# 16n.net
KiCad netlist of a schematic drawn in EAGLE
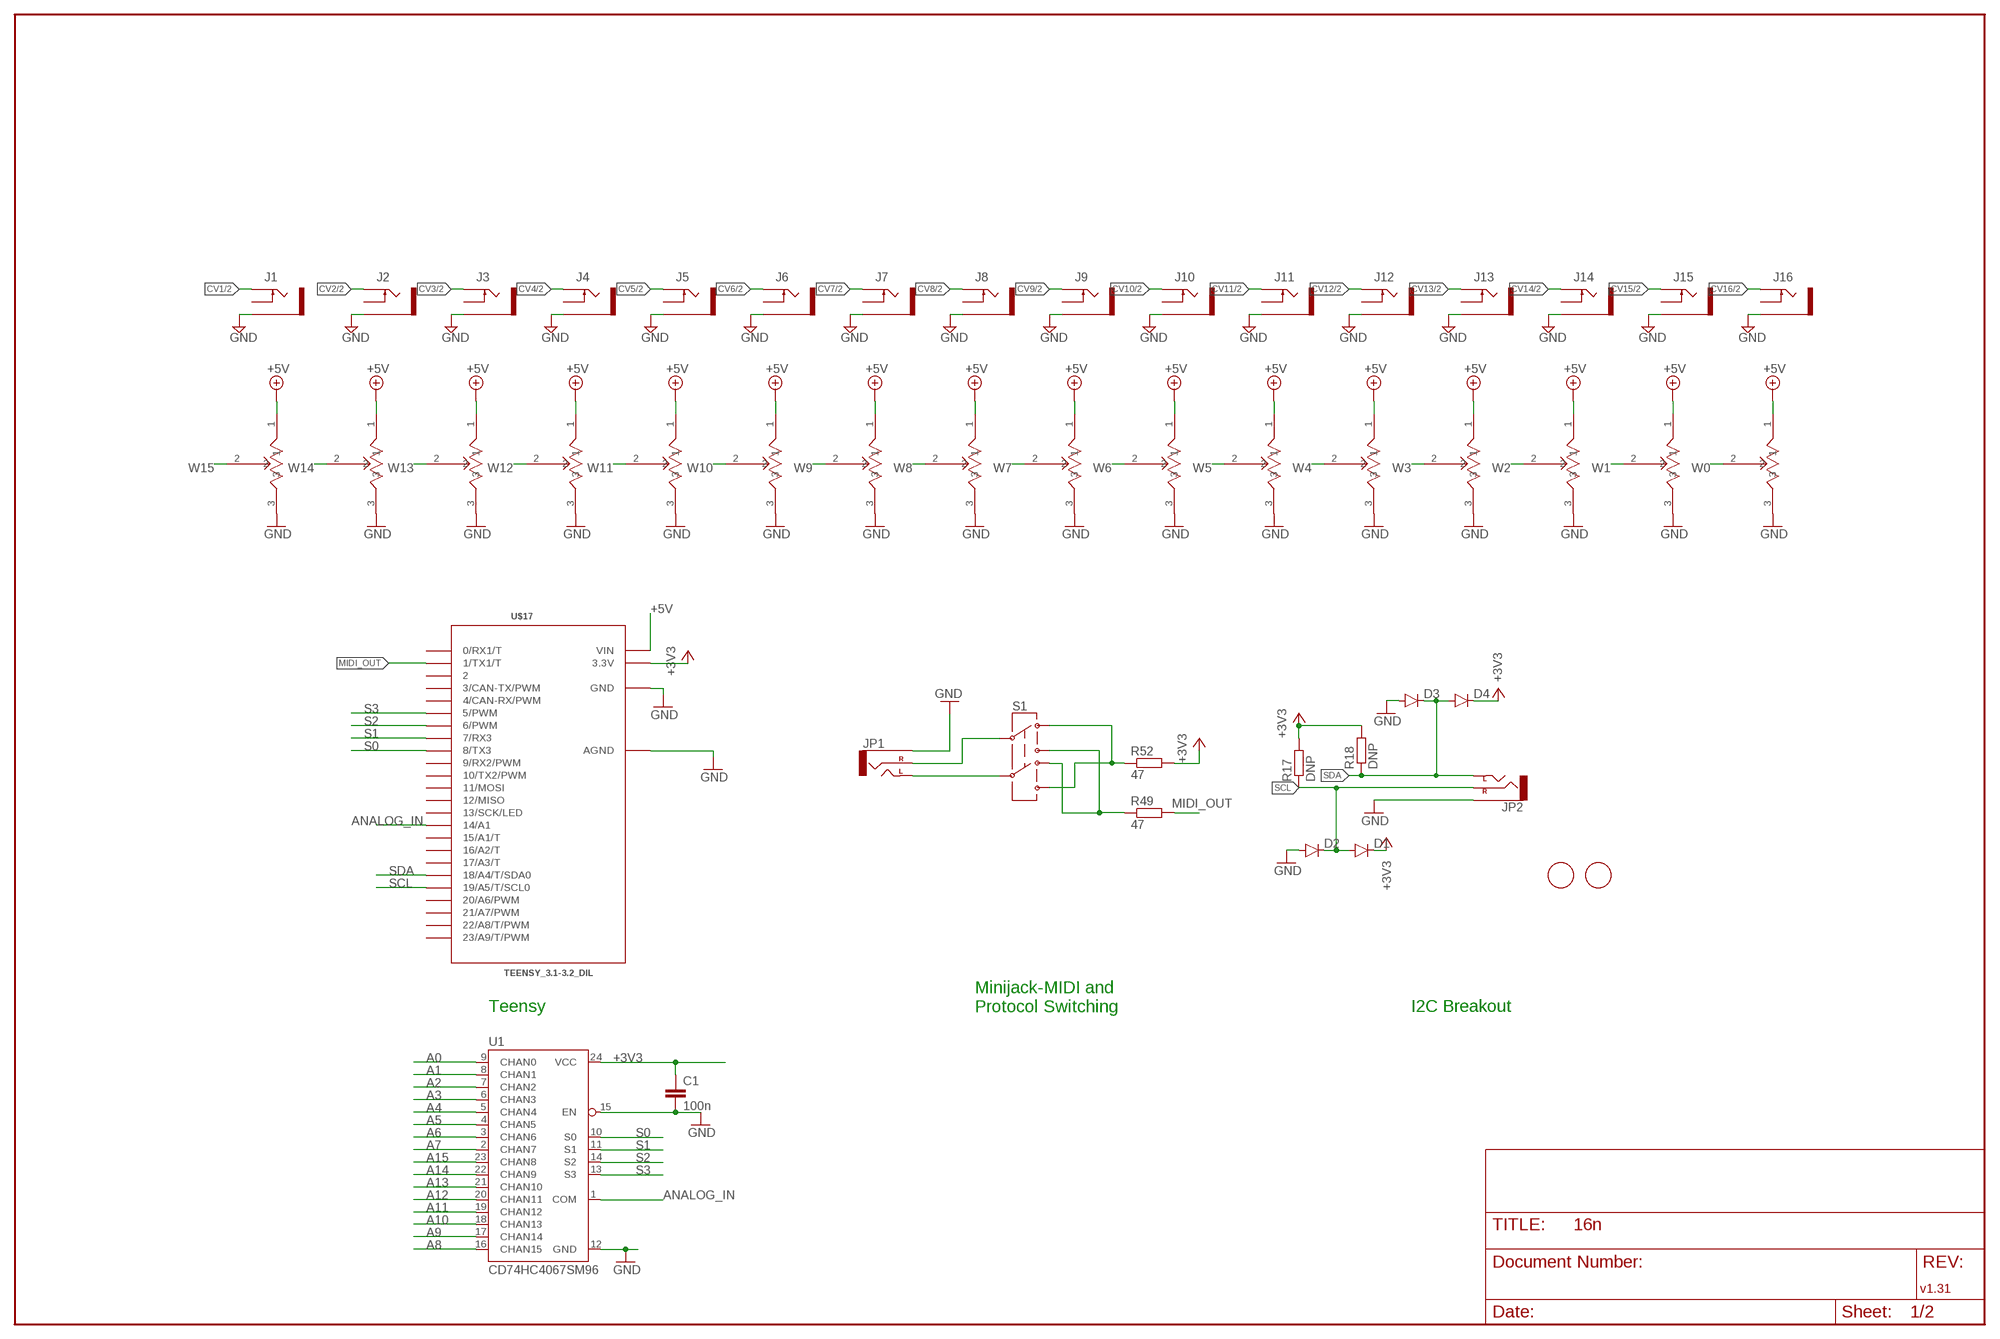
[diagram p0: schematic, sheet 1]
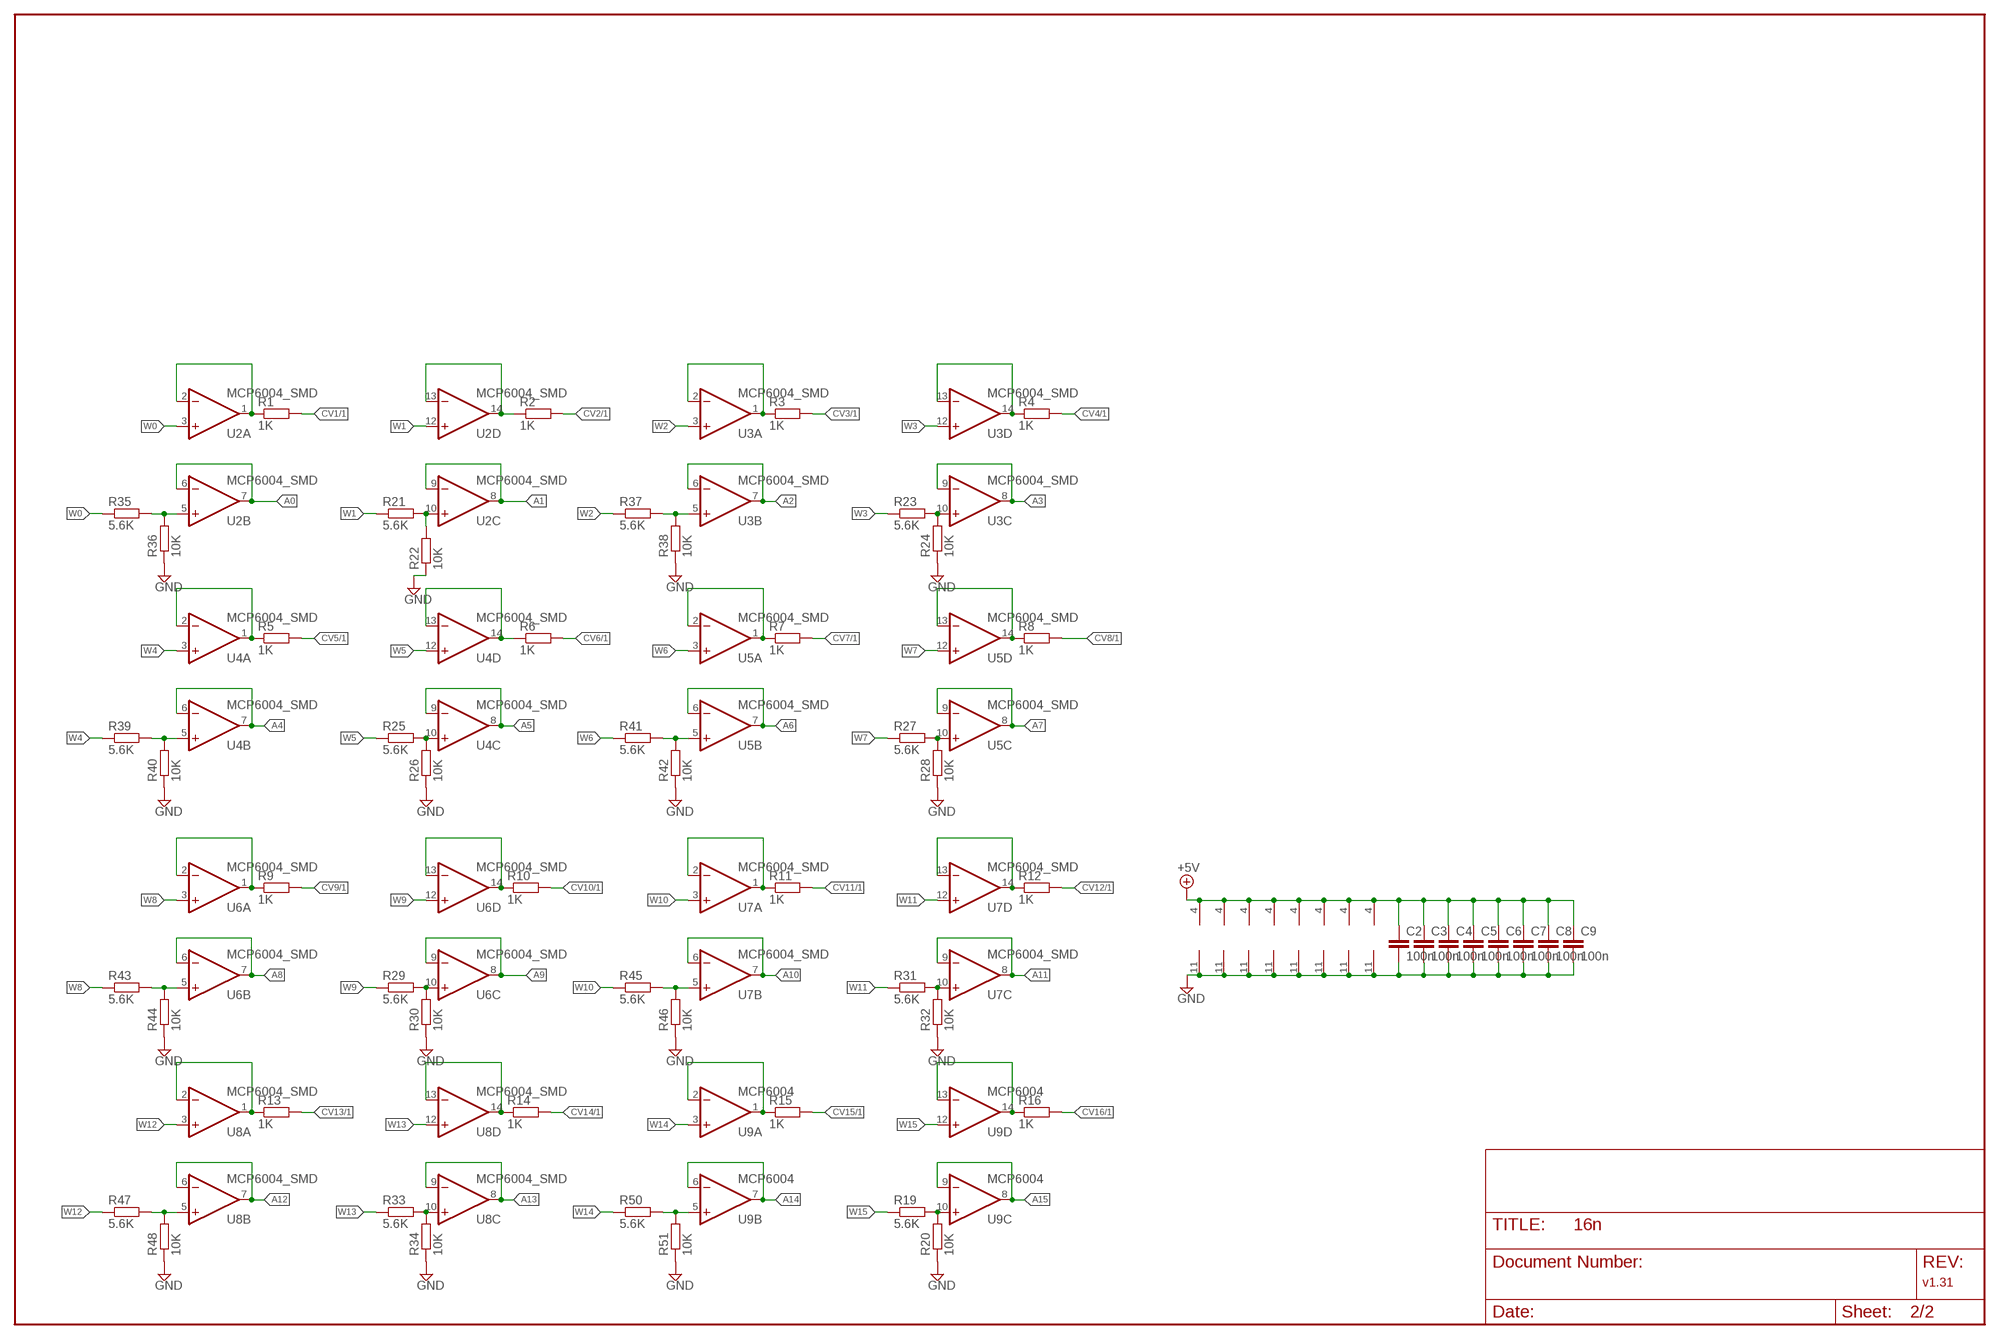
[diagram p1: schematic, sheet 2]

(export (version "E")
  (design (tool "Eeschema 10.0.6"))
  (components
    (comp (ref "C1")
      (value "100n")
      (footprint "eagle-import:C0805")
      (libsource (lib "eagle-import") (part "C-EUC0805"))
    )
    (comp (ref "D1")
      (value "DIODESOD123")
      (footprint "eagle-import:SOD-123")
      (libsource (lib "eagle-import") (part "DIODESOD123"))
    )
    (comp (ref "D2")
      (value "DIODESOD123")
      (footprint "eagle-import:SOD-123")
      (libsource (lib "eagle-import") (part "DIODESOD123"))
    )
    (comp (ref "D3")
      (value "DIODESOD123")
      (footprint "eagle-import:SOD-123")
      (libsource (lib "eagle-import") (part "DIODESOD123"))
    )
    (comp (ref "D4")
      (value "DIODESOD123")
      (footprint "eagle-import:SOD-123")
      (libsource (lib "eagle-import") (part "DIODESOD123"))
    )
    (comp (ref "FID1")
      (value "FIDUCIAL")
      (footprint "eagle-import:FIDUCIAL_1MM")
      (libsource (lib "eagle-import") (part "FIDUCIAL"))
    )
    (comp (ref "FID2")
      (value "FIDUCIAL")
      (footprint "eagle-import:FIDUCIAL_1MM")
      (libsource (lib "eagle-import") (part "FIDUCIAL"))
    )
    (comp (ref "J1")
      (value "PJ302M")
      (footprint "eagle-import:PJ302M")
      (libsource (lib "eagle-import") (part "PJ302M"))
    )
    (comp (ref "J2")
      (value "PJ302M")
      (footprint "eagle-import:PJ302M")
      (libsource (lib "eagle-import") (part "PJ302M"))
    )
    (comp (ref "J3")
      (value "PJ302M")
      (footprint "eagle-import:PJ302M")
      (libsource (lib "eagle-import") (part "PJ302M"))
    )
    (comp (ref "J4")
      (value "PJ302M")
      (footprint "eagle-import:PJ302M")
      (libsource (lib "eagle-import") (part "PJ302M"))
    )
    (comp (ref "J5")
      (value "PJ302M")
      (footprint "eagle-import:PJ302M")
      (libsource (lib "eagle-import") (part "PJ302M"))
    )
    (comp (ref "J6")
      (value "PJ302M")
      (footprint "eagle-import:PJ302M")
      (libsource (lib "eagle-import") (part "PJ302M"))
    )
    (comp (ref "J7")
      (value "PJ302M")
      (footprint "eagle-import:PJ302M")
      (libsource (lib "eagle-import") (part "PJ302M"))
    )
    (comp (ref "J8")
      (value "PJ302M")
      (footprint "eagle-import:PJ302M")
      (libsource (lib "eagle-import") (part "PJ302M"))
    )
    (comp (ref "J9")
      (value "PJ302M")
      (footprint "eagle-import:PJ302M")
      (libsource (lib "eagle-import") (part "PJ302M"))
    )
    (comp (ref "J10")
      (value "PJ302M")
      (footprint "eagle-import:PJ302M")
      (libsource (lib "eagle-import") (part "PJ302M"))
    )
    (comp (ref "J11")
      (value "PJ302M")
      (footprint "eagle-import:PJ302M")
      (libsource (lib "eagle-import") (part "PJ302M"))
    )
    (comp (ref "J12")
      (value "PJ302M")
      (footprint "eagle-import:PJ302M")
      (libsource (lib "eagle-import") (part "PJ302M"))
    )
    (comp (ref "J13")
      (value "PJ302M")
      (footprint "eagle-import:PJ302M")
      (libsource (lib "eagle-import") (part "PJ302M"))
    )
    (comp (ref "J14")
      (value "PJ302M")
      (footprint "eagle-import:PJ302M")
      (libsource (lib "eagle-import") (part "PJ302M"))
    )
    (comp (ref "J15")
      (value "PJ302M")
      (footprint "eagle-import:PJ302M")
      (libsource (lib "eagle-import") (part "PJ302M"))
    )
    (comp (ref "J16")
      (value "PJ302M")
      (footprint "eagle-import:PJ302M")
      (libsource (lib "eagle-import") (part "PJ302M"))
    )
    (comp (ref "JP1")
      (value "AUDIO-JACKPTH")
      (footprint "eagle-import:AUDIO-JACK")
      (libsource (lib "eagle-import") (part "AUDIO-JACKPTH"))
    )
    (comp (ref "JP2")
      (value "AUDIO-JACKPTH")
      (footprint "eagle-import:AUDIO-JACK")
      (libsource (lib "eagle-import") (part "AUDIO-JACKPTH"))
    )
    (comp (ref "R17")
      (value "DNP")
      (footprint "eagle-import:R0805")
      (libsource (lib "eagle-import") (part "R-EU_R0805"))
    )
    (comp (ref "R18")
      (value "DNP")
      (footprint "eagle-import:R0805")
      (libsource (lib "eagle-import") (part "R-EU_R0805"))
    )
    (comp (ref "R49")
      (value "47")
      (footprint "eagle-import:R0805")
      (libsource (lib "eagle-import") (part "R-EU_R0805"))
    )
    (comp (ref "R52")
      (value "47")
      (footprint "eagle-import:R0805")
      (libsource (lib "eagle-import") (part "R-EU_R0805"))
    )
    (comp (ref "S1")
      (value "SWITCH-DPDTEG2211")
      (footprint "eagle-import:EG2211")
      (libsource (lib "eagle-import") (part "SWITCH-DPDTEG2211"))
    )
    (comp (ref "U$1")
      (value "SLIDEPOT-ALPS-60MM")
      (footprint "eagle-import:RS6011SP600")
      (libsource (lib "eagle-import") (part "SLIDEPOT-ALPS-60MM"))
    )
    (comp (ref "U$2")
      (value "SLIDEPOT-ALPS-60MM")
      (footprint "eagle-import:RS6011SP600")
      (libsource (lib "eagle-import") (part "SLIDEPOT-ALPS-60MM"))
    )
    (comp (ref "U$3")
      (value "SLIDEPOT-ALPS-60MM")
      (footprint "eagle-import:RS6011SP600")
      (libsource (lib "eagle-import") (part "SLIDEPOT-ALPS-60MM"))
    )
    (comp (ref "U$4")
      (value "SLIDEPOT-ALPS-60MM")
      (footprint "eagle-import:RS6011SP600")
      (libsource (lib "eagle-import") (part "SLIDEPOT-ALPS-60MM"))
    )
    (comp (ref "U$5")
      (value "SLIDEPOT-ALPS-60MM")
      (footprint "eagle-import:RS6011SP600")
      (libsource (lib "eagle-import") (part "SLIDEPOT-ALPS-60MM"))
    )
    (comp (ref "U$6")
      (value "SLIDEPOT-ALPS-60MM")
      (footprint "eagle-import:RS6011SP600")
      (libsource (lib "eagle-import") (part "SLIDEPOT-ALPS-60MM"))
    )
    (comp (ref "U$7")
      (value "SLIDEPOT-ALPS-60MM")
      (footprint "eagle-import:RS6011SP600")
      (libsource (lib "eagle-import") (part "SLIDEPOT-ALPS-60MM"))
    )
    (comp (ref "U$8")
      (value "SLIDEPOT-ALPS-60MM")
      (footprint "eagle-import:RS6011SP600")
      (libsource (lib "eagle-import") (part "SLIDEPOT-ALPS-60MM"))
    )
    (comp (ref "U$9")
      (value "SLIDEPOT-ALPS-60MM")
      (footprint "eagle-import:RS6011SP600")
      (libsource (lib "eagle-import") (part "SLIDEPOT-ALPS-60MM"))
    )
    (comp (ref "U$10")
      (value "SLIDEPOT-ALPS-60MM")
      (footprint "eagle-import:RS6011SP600")
      (libsource (lib "eagle-import") (part "SLIDEPOT-ALPS-60MM"))
    )
    (comp (ref "U$11")
      (value "SLIDEPOT-ALPS-60MM")
      (footprint "eagle-import:RS6011SP600")
      (libsource (lib "eagle-import") (part "SLIDEPOT-ALPS-60MM"))
    )
    (comp (ref "U$12")
      (value "SLIDEPOT-ALPS-60MM")
      (footprint "eagle-import:RS6011SP600")
      (libsource (lib "eagle-import") (part "SLIDEPOT-ALPS-60MM"))
    )
    (comp (ref "U$13")
      (value "SLIDEPOT-ALPS-60MM")
      (footprint "eagle-import:RS6011SP600")
      (libsource (lib "eagle-import") (part "SLIDEPOT-ALPS-60MM"))
    )
    (comp (ref "U$14")
      (value "SLIDEPOT-ALPS-60MM")
      (footprint "eagle-import:RS6011SP600")
      (libsource (lib "eagle-import") (part "SLIDEPOT-ALPS-60MM"))
    )
    (comp (ref "U$15")
      (value "SLIDEPOT-ALPS-60MM")
      (footprint "eagle-import:RS6011SP600")
      (libsource (lib "eagle-import") (part "SLIDEPOT-ALPS-60MM"))
    )
    (comp (ref "U$16")
      (value "SLIDEPOT-ALPS-60MM")
      (footprint "eagle-import:RS6011SP600")
      (libsource (lib "eagle-import") (part "SLIDEPOT-ALPS-60MM"))
    )
    (comp (ref "U$17")
      (value "TEENSY_3.1-3.2_DIL")
      (footprint "eagle-import:TEENSY_3.0-3.2&LC_DIL")
      (libsource (lib "eagle-import") (part "TEENSY_3.1-3.2_DIL"))
    )
    (comp (ref "U1")
      (value "CD74HC4067SM96")
      (footprint "eagle-import:SOIC127P1030X265-24")
      (libsource (lib "eagle-import") (part "744067SO24"))
    )
    (comp (ref "C2")
      (value "100n")
      (footprint "eagle-import:C0805")
      (libsource (lib "eagle-import") (part "C-EUC0805"))
    )
    (comp (ref "C3")
      (value "100n")
      (footprint "eagle-import:C0805")
      (libsource (lib "eagle-import") (part "C-EUC0805"))
    )
    (comp (ref "C4")
      (value "100n")
      (footprint "eagle-import:C0805")
      (libsource (lib "eagle-import") (part "C-EUC0805"))
    )
    (comp (ref "C5")
      (value "100n")
      (footprint "eagle-import:C0805")
      (libsource (lib "eagle-import") (part "C-EUC0805"))
    )
    (comp (ref "C6")
      (value "100n")
      (footprint "eagle-import:C0805")
      (libsource (lib "eagle-import") (part "C-EUC0805"))
    )
    (comp (ref "C7")
      (value "100n")
      (footprint "eagle-import:C0805")
      (libsource (lib "eagle-import") (part "C-EUC0805"))
    )
    (comp (ref "C8")
      (value "100n")
      (footprint "eagle-import:C0805")
      (libsource (lib "eagle-import") (part "C-EUC0805"))
    )
    (comp (ref "C9")
      (value "100n")
      (footprint "eagle-import:C0805")
      (libsource (lib "eagle-import") (part "C-EUC0805"))
    )
    (comp (ref "R1")
      (value "1K")
      (footprint "eagle-import:R0805")
      (libsource (lib "eagle-import") (part "R-EU_R0805"))
    )
    (comp (ref "R2")
      (value "1K")
      (footprint "eagle-import:R0805")
      (libsource (lib "eagle-import") (part "R-EU_R0805"))
    )
    (comp (ref "R3")
      (value "1K")
      (footprint "eagle-import:R0805")
      (libsource (lib "eagle-import") (part "R-EU_R0805"))
    )
    (comp (ref "R4")
      (value "1K")
      (footprint "eagle-import:R0805")
      (libsource (lib "eagle-import") (part "R-EU_R0805"))
    )
    (comp (ref "R5")
      (value "1K")
      (footprint "eagle-import:R0805")
      (libsource (lib "eagle-import") (part "R-EU_R0805"))
    )
    (comp (ref "R6")
      (value "1K")
      (footprint "eagle-import:R0805")
      (libsource (lib "eagle-import") (part "R-EU_R0805"))
    )
    (comp (ref "R7")
      (value "1K")
      (footprint "eagle-import:R0805")
      (libsource (lib "eagle-import") (part "R-EU_R0805"))
    )
    (comp (ref "R8")
      (value "1K")
      (footprint "eagle-import:R0805")
      (libsource (lib "eagle-import") (part "R-EU_R0805"))
    )
    (comp (ref "R9")
      (value "1K")
      (footprint "eagle-import:R0805")
      (libsource (lib "eagle-import") (part "R-EU_R0805"))
    )
    (comp (ref "R10")
      (value "1K")
      (footprint "eagle-import:R0805")
      (libsource (lib "eagle-import") (part "R-EU_R0805"))
    )
    (comp (ref "R11")
      (value "1K")
      (footprint "eagle-import:R0805")
      (libsource (lib "eagle-import") (part "R-EU_R0805"))
    )
    (comp (ref "R12")
      (value "1K")
      (footprint "eagle-import:R0805")
      (libsource (lib "eagle-import") (part "R-EU_R0805"))
    )
    (comp (ref "R13")
      (value "1K")
      (footprint "eagle-import:R0805")
      (libsource (lib "eagle-import") (part "R-EU_R0805"))
    )
    (comp (ref "R14")
      (value "1K")
      (footprint "eagle-import:R0805")
      (libsource (lib "eagle-import") (part "R-EU_R0805"))
    )
    (comp (ref "R15")
      (value "1K")
      (footprint "eagle-import:R0805")
      (libsource (lib "eagle-import") (part "R-EU_R0805"))
    )
    (comp (ref "R16")
      (value "1K")
      (footprint "eagle-import:R0805")
      (libsource (lib "eagle-import") (part "R-EU_R0805"))
    )
    (comp (ref "R19")
      (value "5.6K")
      (footprint "eagle-import:R0805")
      (libsource (lib "eagle-import") (part "R-EU_R0805"))
    )
    (comp (ref "R20")
      (value "10K")
      (footprint "eagle-import:R0805")
      (libsource (lib "eagle-import") (part "R-EU_R0805"))
    )
    (comp (ref "R21")
      (value "5.6K")
      (footprint "eagle-import:R0805")
      (libsource (lib "eagle-import") (part "R-EU_R0805"))
    )
    (comp (ref "R22")
      (value "10K")
      (footprint "eagle-import:R0805")
      (libsource (lib "eagle-import") (part "R-EU_R0805"))
    )
    (comp (ref "R23")
      (value "5.6K")
      (footprint "eagle-import:R0805")
      (libsource (lib "eagle-import") (part "R-EU_R0805"))
    )
    (comp (ref "R24")
      (value "10K")
      (footprint "eagle-import:R0805")
      (libsource (lib "eagle-import") (part "R-EU_R0805"))
    )
    (comp (ref "R25")
      (value "5.6K")
      (footprint "eagle-import:R0805")
      (libsource (lib "eagle-import") (part "R-EU_R0805"))
    )
    (comp (ref "R26")
      (value "10K")
      (footprint "eagle-import:R0805")
      (libsource (lib "eagle-import") (part "R-EU_R0805"))
    )
    (comp (ref "R27")
      (value "5.6K")
      (footprint "eagle-import:R0805")
      (libsource (lib "eagle-import") (part "R-EU_R0805"))
    )
    (comp (ref "R28")
      (value "10K")
      (footprint "eagle-import:R0805")
      (libsource (lib "eagle-import") (part "R-EU_R0805"))
    )
    (comp (ref "R29")
      (value "5.6K")
      (footprint "eagle-import:R0805")
      (libsource (lib "eagle-import") (part "R-EU_R0805"))
    )
    (comp (ref "R30")
      (value "10K")
      (footprint "eagle-import:R0805")
      (libsource (lib "eagle-import") (part "R-EU_R0805"))
    )
    (comp (ref "R31")
      (value "5.6K")
      (footprint "eagle-import:R0805")
      (libsource (lib "eagle-import") (part "R-EU_R0805"))
    )
    (comp (ref "R32")
      (value "10K")
      (footprint "eagle-import:R0805")
      (libsource (lib "eagle-import") (part "R-EU_R0805"))
    )
    (comp (ref "R33")
      (value "5.6K")
      (footprint "eagle-import:R0805")
      (libsource (lib "eagle-import") (part "R-EU_R0805"))
    )
    (comp (ref "R34")
      (value "10K")
      (footprint "eagle-import:R0805")
      (libsource (lib "eagle-import") (part "R-EU_R0805"))
    )
    (comp (ref "R35")
      (value "5.6K")
      (footprint "eagle-import:R0805")
      (libsource (lib "eagle-import") (part "R-EU_R0805"))
    )
    (comp (ref "R36")
      (value "10K")
      (footprint "eagle-import:R0805")
      (libsource (lib "eagle-import") (part "R-EU_R0805"))
    )
    (comp (ref "R37")
      (value "5.6K")
      (footprint "eagle-import:R0805")
      (libsource (lib "eagle-import") (part "R-EU_R0805"))
    )
    (comp (ref "R38")
      (value "10K")
      (footprint "eagle-import:R0805")
      (libsource (lib "eagle-import") (part "R-EU_R0805"))
    )
    (comp (ref "R39")
      (value "5.6K")
      (footprint "eagle-import:R0805")
      (libsource (lib "eagle-import") (part "R-EU_R0805"))
    )
    (comp (ref "R40")
      (value "10K")
      (footprint "eagle-import:R0805")
      (libsource (lib "eagle-import") (part "R-EU_R0805"))
    )
    (comp (ref "R41")
      (value "5.6K")
      (footprint "eagle-import:R0805")
      (libsource (lib "eagle-import") (part "R-EU_R0805"))
    )
    (comp (ref "R42")
      (value "10K")
      (footprint "eagle-import:R0805")
      (libsource (lib "eagle-import") (part "R-EU_R0805"))
    )
    (comp (ref "R43")
      (value "5.6K")
      (footprint "eagle-import:R0805")
      (libsource (lib "eagle-import") (part "R-EU_R0805"))
    )
    (comp (ref "R44")
      (value "10K")
      (footprint "eagle-import:R0805")
      (libsource (lib "eagle-import") (part "R-EU_R0805"))
    )
    (comp (ref "R45")
      (value "5.6K")
      (footprint "eagle-import:R0805")
      (libsource (lib "eagle-import") (part "R-EU_R0805"))
    )
    (comp (ref "R46")
      (value "10K")
      (footprint "eagle-import:R0805")
      (libsource (lib "eagle-import") (part "R-EU_R0805"))
    )
    (comp (ref "R47")
      (value "5.6K")
      (footprint "eagle-import:R0805")
      (libsource (lib "eagle-import") (part "R-EU_R0805"))
    )
    (comp (ref "R48")
      (value "10K")
      (footprint "eagle-import:R0805")
      (libsource (lib "eagle-import") (part "R-EU_R0805"))
    )
    (comp (ref "R50")
      (value "5.6K")
      (footprint "eagle-import:R0805")
      (libsource (lib "eagle-import") (part "R-EU_R0805"))
    )
    (comp (ref "R51")
      (value "10K")
      (footprint "eagle-import:R0805")
      (libsource (lib "eagle-import") (part "R-EU_R0805"))
    )
    (comp (ref "U2")
      (value "MCP6004_SMD")
      (footprint "eagle-import:SO14")
      (libsource (lib "eagle-import") (part "MCP6004_SMD"))
    )
    (comp (ref "U3")
      (value "MCP6004_SMD")
      (footprint "eagle-import:SO14")
      (libsource (lib "eagle-import") (part "MCP6004_SMD"))
    )
    (comp (ref "U4")
      (value "MCP6004_SMD")
      (footprint "eagle-import:SO14")
      (libsource (lib "eagle-import") (part "MCP6004_SMD"))
    )
    (comp (ref "U5")
      (value "MCP6004_SMD")
      (footprint "eagle-import:SO14")
      (libsource (lib "eagle-import") (part "MCP6004_SMD"))
    )
    (comp (ref "U6")
      (value "MCP6004_SMD")
      (footprint "eagle-import:SO14")
      (libsource (lib "eagle-import") (part "MCP6004_SMD"))
    )
    (comp (ref "U7")
      (value "MCP6004_SMD")
      (footprint "eagle-import:SO14")
      (libsource (lib "eagle-import") (part "MCP6004_SMD"))
    )
    (comp (ref "U8")
      (value "MCP6004_SMD")
      (footprint "eagle-import:SO14")
      (libsource (lib "eagle-import") (part "MCP6004_SMD"))
    )
    (comp (ref "U9")
      (value "MCP6004")
      (footprint "eagle-import:SO14")
      (libsource (lib "eagle-import") (part "MCP6004_SMD"))
    )
  )
  (nets
    (net (code "1") (name "+3V3") (class "Default")
      (node (ref "C1") (pin "1") (pinfunction "1_1") (pintype "passive"))
      (node (ref "D1") (pin "C") (pinfunction "C_C") (pintype "passive"))
      (node (ref "D4") (pin "C") (pinfunction "C_C") (pintype "passive"))
      (node (ref "R17") (pin "2") (pinfunction "2_2") (pintype "passive"))
      (node (ref "R18") (pin "2") (pinfunction "2_2") (pintype "passive"))
      (node (ref "R52") (pin "2") (pinfunction "2_2") (pintype "passive"))
      (node (ref "U$17") (pin "3.3V") (pinfunction "3.3V_3.3V") (pintype "power_in"))
      (node (ref "U1") (pin "24") (pinfunction "VCC_24") (pintype "bidirectional"))
    )
    (net (code "2") (name "+5V") (class "Default")
      (node (ref "C2") (pin "1") (pinfunction "1_1") (pintype "passive"))
      (node (ref "C3") (pin "1") (pinfunction "1_1") (pintype "passive"))
      (node (ref "C4") (pin "1") (pinfunction "1_1") (pintype "passive"))
      (node (ref "C5") (pin "1") (pinfunction "1_1") (pintype "passive"))
      (node (ref "C6") (pin "1") (pinfunction "1_1") (pintype "passive"))
      (node (ref "C7") (pin "1") (pinfunction "1_1") (pintype "passive"))
      (node (ref "C8") (pin "1") (pinfunction "1_1") (pintype "passive"))
      (node (ref "C9") (pin "1") (pinfunction "1_1") (pintype "passive"))
      (node (ref "U$1") (pin "1") (pinfunction "1_1") (pintype "bidirectional"))
      (node (ref "U$10") (pin "1") (pinfunction "1_1") (pintype "bidirectional"))
      (node (ref "U$11") (pin "1") (pinfunction "1_1") (pintype "bidirectional"))
      (node (ref "U$12") (pin "1") (pinfunction "1_1") (pintype "bidirectional"))
      (node (ref "U$13") (pin "1") (pinfunction "1_1") (pintype "bidirectional"))
      (node (ref "U$14") (pin "1") (pinfunction "1_1") (pintype "bidirectional"))
      (node (ref "U$15") (pin "1") (pinfunction "1_1") (pintype "bidirectional"))
      (node (ref "U$16") (pin "1") (pinfunction "1_1") (pintype "bidirectional"))
      (node (ref "U$17") (pin "VIN") (pinfunction "VIN_VIN") (pintype "power_in"))
      (node (ref "U$2") (pin "1") (pinfunction "1_1") (pintype "bidirectional"))
      (node (ref "U$3") (pin "1") (pinfunction "1_1") (pintype "bidirectional"))
      (node (ref "U$4") (pin "1") (pinfunction "1_1") (pintype "bidirectional"))
      (node (ref "U$5") (pin "1") (pinfunction "1_1") (pintype "bidirectional"))
      (node (ref "U$6") (pin "1") (pinfunction "1_1") (pintype "bidirectional"))
      (node (ref "U$7") (pin "1") (pinfunction "1_1") (pintype "bidirectional"))
      (node (ref "U$8") (pin "1") (pinfunction "1_1") (pintype "bidirectional"))
      (node (ref "U$9") (pin "1") (pinfunction "1_1") (pintype "bidirectional"))
      (node (ref "U2") (pin "4") (pinfunction "V+_4") (pintype "power_in"))
      (node (ref "U3") (pin "4") (pinfunction "V+_4") (pintype "power_in"))
      (node (ref "U4") (pin "4") (pinfunction "V+_4") (pintype "power_in"))
      (node (ref "U5") (pin "4") (pinfunction "V+_4") (pintype "power_in"))
      (node (ref "U6") (pin "4") (pinfunction "V+_4") (pintype "power_in"))
      (node (ref "U7") (pin "4") (pinfunction "V+_4") (pintype "power_in"))
      (node (ref "U8") (pin "4") (pinfunction "V+_4") (pintype "power_in"))
      (node (ref "U9") (pin "4") (pinfunction "V+_4") (pintype "power_in"))
    )
    (net (code "3") (name "A0") (class "Default")
      (node (ref "U1") (pin "9") (pinfunction "CHAN0_9") (pintype "bidirectional"))
      (node (ref "U2") (pin "6") (pinfunction "-IN_6") (pintype "input"))
      (node (ref "U2") (pin "7") (pinfunction "OUT_7") (pintype "output"))
    )
    (net (code "4") (name "A1") (class "Default")
      (node (ref "U1") (pin "8") (pinfunction "CHAN1_8") (pintype "bidirectional"))
      (node (ref "U2") (pin "8") (pinfunction "OUT_8") (pintype "output"))
      (node (ref "U2") (pin "9") (pinfunction "-IN_9") (pintype "input"))
    )
    (net (code "5") (name "A2") (class "Default")
      (node (ref "U1") (pin "7") (pinfunction "CHAN2_7") (pintype "bidirectional"))
      (node (ref "U3") (pin "6") (pinfunction "-IN_6") (pintype "input"))
      (node (ref "U3") (pin "7") (pinfunction "OUT_7") (pintype "output"))
    )
    (net (code "6") (name "A3") (class "Default")
      (node (ref "U1") (pin "6") (pinfunction "CHAN3_6") (pintype "bidirectional"))
      (node (ref "U3") (pin "8") (pinfunction "OUT_8") (pintype "output"))
      (node (ref "U3") (pin "9") (pinfunction "-IN_9") (pintype "input"))
    )
    (net (code "7") (name "A4") (class "Default")
      (node (ref "U1") (pin "5") (pinfunction "CHAN4_5") (pintype "bidirectional"))
      (node (ref "U4") (pin "6") (pinfunction "-IN_6") (pintype "input"))
      (node (ref "U4") (pin "7") (pinfunction "OUT_7") (pintype "output"))
    )
    (net (code "8") (name "A5") (class "Default")
      (node (ref "U1") (pin "4") (pinfunction "CHAN5_4") (pintype "bidirectional"))
      (node (ref "U4") (pin "8") (pinfunction "OUT_8") (pintype "output"))
      (node (ref "U4") (pin "9") (pinfunction "-IN_9") (pintype "input"))
    )
    (net (code "9") (name "A6") (class "Default")
      (node (ref "U1") (pin "3") (pinfunction "CHAN6_3") (pintype "bidirectional"))
      (node (ref "U5") (pin "6") (pinfunction "-IN_6") (pintype "input"))
      (node (ref "U5") (pin "7") (pinfunction "OUT_7") (pintype "output"))
    )
    (net (code "10") (name "A7") (class "Default")
      (node (ref "U1") (pin "2") (pinfunction "CHAN7_2") (pintype "bidirectional"))
      (node (ref "U5") (pin "8") (pinfunction "OUT_8") (pintype "output"))
      (node (ref "U5") (pin "9") (pinfunction "-IN_9") (pintype "input"))
    )
    (net (code "11") (name "A8") (class "Default")
      (node (ref "U1") (pin "16") (pinfunction "CHAN15_16") (pintype "bidirectional"))
      (node (ref "U6") (pin "6") (pinfunction "-IN_6") (pintype "input"))
      (node (ref "U6") (pin "7") (pinfunction "OUT_7") (pintype "output"))
    )
    (net (code "12") (name "A9") (class "Default")
      (node (ref "U1") (pin "17") (pinfunction "CHAN14_17") (pintype "bidirectional"))
      (node (ref "U6") (pin "8") (pinfunction "OUT_8") (pintype "output"))
      (node (ref "U6") (pin "9") (pinfunction "-IN_9") (pintype "input"))
    )
    (net (code "13") (name "A10") (class "Default")
      (node (ref "U1") (pin "18") (pinfunction "CHAN13_18") (pintype "bidirectional"))
      (node (ref "U7") (pin "6") (pinfunction "-IN_6") (pintype "input"))
      (node (ref "U7") (pin "7") (pinfunction "OUT_7") (pintype "output"))
    )
    (net (code "14") (name "A11") (class "Default")
      (node (ref "U1") (pin "19") (pinfunction "CHAN12_19") (pintype "bidirectional"))
      (node (ref "U7") (pin "8") (pinfunction "OUT_8") (pintype "output"))
      (node (ref "U7") (pin "9") (pinfunction "-IN_9") (pintype "input"))
    )
    (net (code "15") (name "A12") (class "Default")
      (node (ref "U1") (pin "20") (pinfunction "CHAN11_20") (pintype "bidirectional"))
      (node (ref "U8") (pin "6") (pinfunction "-IN_6") (pintype "input"))
      (node (ref "U8") (pin "7") (pinfunction "OUT_7") (pintype "output"))
    )
    (net (code "16") (name "A13") (class "Default")
      (node (ref "U1") (pin "21") (pinfunction "CHAN10_21") (pintype "bidirectional"))
      (node (ref "U8") (pin "8") (pinfunction "OUT_8") (pintype "output"))
      (node (ref "U8") (pin "9") (pinfunction "-IN_9") (pintype "input"))
    )
    (net (code "17") (name "A14") (class "Default")
      (node (ref "U1") (pin "22") (pinfunction "CHAN9_22") (pintype "bidirectional"))
      (node (ref "U9") (pin "6") (pinfunction "-IN_6") (pintype "input"))
      (node (ref "U9") (pin "7") (pinfunction "OUT_7") (pintype "output"))
    )
    (net (code "18") (name "A15") (class "Default")
      (node (ref "U1") (pin "23") (pinfunction "CHAN8_23") (pintype "bidirectional"))
      (node (ref "U9") (pin "8") (pinfunction "OUT_8") (pintype "output"))
      (node (ref "U9") (pin "9") (pinfunction "-IN_9") (pintype "input"))
    )
    (net (code "19") (name "ANALOG_IN") (class "Default")
      (node (ref "U$17") (pin "14/A0") (pinfunction "14/A1_14/A0") (pintype "bidirectional"))
      (node (ref "U1") (pin "1") (pinfunction "COM_1") (pintype "bidirectional"))
    )
    (net (code "20") (name "CV1") (class "Default")
      (node (ref "J1") (pin "TIP") (pinfunction "TIP_TIP") (pintype "passive"))
      (node (ref "R1") (pin "2") (pinfunction "2_2") (pintype "passive"))
    )
    (net (code "21") (name "CV2") (class "Default")
      (node (ref "J2") (pin "TIP") (pinfunction "TIP_TIP") (pintype "passive"))
      (node (ref "R2") (pin "2") (pinfunction "2_2") (pintype "passive"))
    )
    (net (code "22") (name "CV3") (class "Default")
      (node (ref "J3") (pin "TIP") (pinfunction "TIP_TIP") (pintype "passive"))
      (node (ref "R3") (pin "2") (pinfunction "2_2") (pintype "passive"))
    )
    (net (code "23") (name "CV4") (class "Default")
      (node (ref "J4") (pin "TIP") (pinfunction "TIP_TIP") (pintype "passive"))
      (node (ref "R4") (pin "2") (pinfunction "2_2") (pintype "passive"))
    )
    (net (code "24") (name "CV5") (class "Default")
      (node (ref "J5") (pin "TIP") (pinfunction "TIP_TIP") (pintype "passive"))
      (node (ref "R5") (pin "2") (pinfunction "2_2") (pintype "passive"))
    )
    (net (code "25") (name "CV6") (class "Default")
      (node (ref "J6") (pin "TIP") (pinfunction "TIP_TIP") (pintype "passive"))
      (node (ref "R6") (pin "2") (pinfunction "2_2") (pintype "passive"))
    )
    (net (code "26") (name "CV7") (class "Default")
      (node (ref "J7") (pin "TIP") (pinfunction "TIP_TIP") (pintype "passive"))
      (node (ref "R7") (pin "2") (pinfunction "2_2") (pintype "passive"))
    )
    (net (code "27") (name "CV8") (class "Default")
      (node (ref "J8") (pin "TIP") (pinfunction "TIP_TIP") (pintype "passive"))
      (node (ref "R8") (pin "2") (pinfunction "2_2") (pintype "passive"))
    )
    (net (code "28") (name "CV9") (class "Default")
      (node (ref "J9") (pin "TIP") (pinfunction "TIP_TIP") (pintype "passive"))
      (node (ref "R9") (pin "2") (pinfunction "2_2") (pintype "passive"))
    )
    (net (code "29") (name "CV10") (class "Default")
      (node (ref "J10") (pin "TIP") (pinfunction "TIP_TIP") (pintype "passive"))
      (node (ref "R10") (pin "2") (pinfunction "2_2") (pintype "passive"))
    )
    (net (code "30") (name "CV11") (class "Default")
      (node (ref "J11") (pin "TIP") (pinfunction "TIP_TIP") (pintype "passive"))
      (node (ref "R11") (pin "2") (pinfunction "2_2") (pintype "passive"))
    )
    (net (code "31") (name "CV12") (class "Default")
      (node (ref "J12") (pin "TIP") (pinfunction "TIP_TIP") (pintype "passive"))
      (node (ref "R12") (pin "2") (pinfunction "2_2") (pintype "passive"))
    )
    (net (code "32") (name "CV13") (class "Default")
      (node (ref "J13") (pin "TIP") (pinfunction "TIP_TIP") (pintype "passive"))
      (node (ref "R13") (pin "2") (pinfunction "2_2") (pintype "passive"))
    )
    (net (code "33") (name "CV14") (class "Default")
      (node (ref "J14") (pin "TIP") (pinfunction "TIP_TIP") (pintype "passive"))
      (node (ref "R14") (pin "2") (pinfunction "2_2") (pintype "passive"))
    )
    (net (code "34") (name "CV15") (class "Default")
      (node (ref "J15") (pin "TIP") (pinfunction "TIP_TIP") (pintype "passive"))
      (node (ref "R15") (pin "2") (pinfunction "2_2") (pintype "passive"))
    )
    (net (code "35") (name "CV16") (class "Default")
      (node (ref "J16") (pin "TIP") (pinfunction "TIP_TIP") (pintype "passive"))
      (node (ref "R16") (pin "2") (pinfunction "2_2") (pintype "passive"))
    )
    (net (code "36") (name "GND") (class "Default")
      (node (ref "C1") (pin "2") (pinfunction "2_2") (pintype "passive"))
      (node (ref "C2") (pin "2") (pinfunction "2_2") (pintype "passive"))
      (node (ref "C3") (pin "2") (pinfunction "2_2") (pintype "passive"))
      (node (ref "C4") (pin "2") (pinfunction "2_2") (pintype "passive"))
      (node (ref "C5") (pin "2") (pinfunction "2_2") (pintype "passive"))
      (node (ref "C6") (pin "2") (pinfunction "2_2") (pintype "passive"))
      (node (ref "C7") (pin "2") (pinfunction "2_2") (pintype "passive"))
      (node (ref "C8") (pin "2") (pinfunction "2_2") (pintype "passive"))
      (node (ref "C9") (pin "2") (pinfunction "2_2") (pintype "passive"))
      (node (ref "D2") (pin "A") (pinfunction "A_A") (pintype "passive"))
      (node (ref "D3") (pin "A") (pinfunction "A_A") (pintype "passive"))
      (node (ref "J1") (pin "GND") (pinfunction "SLEEVE_GND") (pintype "passive"))
      (node (ref "J10") (pin "GND") (pinfunction "SLEEVE_GND") (pintype "passive"))
      (node (ref "J11") (pin "GND") (pinfunction "SLEEVE_GND") (pintype "passive"))
      (node (ref "J12") (pin "GND") (pinfunction "SLEEVE_GND") (pintype "passive"))
      (node (ref "J13") (pin "GND") (pinfunction "SLEEVE_GND") (pintype "passive"))
      (node (ref "J14") (pin "GND") (pinfunction "SLEEVE_GND") (pintype "passive"))
      (node (ref "J15") (pin "GND") (pinfunction "SLEEVE_GND") (pintype "passive"))
      (node (ref "J16") (pin "GND") (pinfunction "SLEEVE_GND") (pintype "passive"))
      (node (ref "J2") (pin "GND") (pinfunction "SLEEVE_GND") (pintype "passive"))
      (node (ref "J3") (pin "GND") (pinfunction "SLEEVE_GND") (pintype "passive"))
      (node (ref "J4") (pin "GND") (pinfunction "SLEEVE_GND") (pintype "passive"))
      (node (ref "J5") (pin "GND") (pinfunction "SLEEVE_GND") (pintype "passive"))
      (node (ref "J6") (pin "GND") (pinfunction "SLEEVE_GND") (pintype "passive"))
      (node (ref "J7") (pin "GND") (pinfunction "SLEEVE_GND") (pintype "passive"))
      (node (ref "J8") (pin "GND") (pinfunction "SLEEVE_GND") (pintype "passive"))
      (node (ref "J9") (pin "GND") (pinfunction "SLEEVE_GND") (pintype "passive"))
      (node (ref "JP1") (pin "SLEEVE") (pinfunction "SLEEVE_SLEEVE") (pintype "bidirectional"))
      (node (ref "JP2") (pin "SLEEVE") (pinfunction "SLEEVE_SLEEVE") (pintype "bidirectional"))
      (node (ref "R20") (pin "1") (pinfunction "1_1") (pintype "passive"))
      (node (ref "R22") (pin "1") (pinfunction "1_1") (pintype "passive"))
      (node (ref "R24") (pin "1") (pinfunction "1_1") (pintype "passive"))
      (node (ref "R26") (pin "1") (pinfunction "1_1") (pintype "passive"))
      (node (ref "R28") (pin "1") (pinfunction "1_1") (pintype "passive"))
      (node (ref "R30") (pin "1") (pinfunction "1_1") (pintype "passive"))
      (node (ref "R32") (pin "1") (pinfunction "1_1") (pintype "passive"))
      (node (ref "R34") (pin "1") (pinfunction "1_1") (pintype "passive"))
      (node (ref "R36") (pin "1") (pinfunction "1_1") (pintype "passive"))
      (node (ref "R38") (pin "1") (pinfunction "1_1") (pintype "passive"))
      (node (ref "R40") (pin "1") (pinfunction "1_1") (pintype "passive"))
      (node (ref "R42") (pin "1") (pinfunction "1_1") (pintype "passive"))
      (node (ref "R44") (pin "1") (pinfunction "1_1") (pintype "passive"))
      (node (ref "R46") (pin "1") (pinfunction "1_1") (pintype "passive"))
      (node (ref "R48") (pin "1") (pinfunction "1_1") (pintype "passive"))
      (node (ref "R51") (pin "1") (pinfunction "1_1") (pintype "passive"))
      (node (ref "U$1") (pin "3") (pinfunction "3_3") (pintype "bidirectional"))
      (node (ref "U$10") (pin "3") (pinfunction "3_3") (pintype "bidirectional"))
      (node (ref "U$11") (pin "3") (pinfunction "3_3") (pintype "bidirectional"))
      (node (ref "U$12") (pin "3") (pinfunction "3_3") (pintype "bidirectional"))
      (node (ref "U$13") (pin "3") (pinfunction "3_3") (pintype "bidirectional"))
      (node (ref "U$14") (pin "3") (pinfunction "3_3") (pintype "bidirectional"))
      (node (ref "U$15") (pin "3") (pinfunction "3_3") (pintype "bidirectional"))
      (node (ref "U$16") (pin "3") (pinfunction "3_3") (pintype "bidirectional"))
      (node (ref "U$17") (pin "AGND") (pinfunction "AGND_AGND") (pintype "power_in"))
      (node (ref "U$17") (pin "GND") (pinfunction "GND_GND") (pintype "power_in"))
      (node (ref "U$2") (pin "3") (pinfunction "3_3") (pintype "bidirectional"))
      (node (ref "U$3") (pin "3") (pinfunction "3_3") (pintype "bidirectional"))
      (node (ref "U$4") (pin "3") (pinfunction "3_3") (pintype "bidirectional"))
      (node (ref "U$5") (pin "3") (pinfunction "3_3") (pintype "bidirectional"))
      (node (ref "U$6") (pin "3") (pinfunction "3_3") (pintype "bidirectional"))
      (node (ref "U$7") (pin "3") (pinfunction "3_3") (pintype "bidirectional"))
      (node (ref "U$8") (pin "3") (pinfunction "3_3") (pintype "bidirectional"))
      (node (ref "U$9") (pin "3") (pinfunction "3_3") (pintype "bidirectional"))
      (node (ref "U1") (pin "12") (pinfunction "GND_12") (pintype "bidirectional"))
      (node (ref "U1") (pin "15") (pinfunction "EN_15") (pintype "input"))
      (node (ref "U2") (pin "11") (pinfunction "V-_11") (pintype "power_in"))
      (node (ref "U3") (pin "11") (pinfunction "V-_11") (pintype "power_in"))
      (node (ref "U4") (pin "11") (pinfunction "V-_11") (pintype "power_in"))
      (node (ref "U5") (pin "11") (pinfunction "V-_11") (pintype "power_in"))
      (node (ref "U6") (pin "11") (pinfunction "V-_11") (pintype "power_in"))
      (node (ref "U7") (pin "11") (pinfunction "V-_11") (pintype "power_in"))
      (node (ref "U8") (pin "11") (pinfunction "V-_11") (pintype "power_in"))
      (node (ref "U9") (pin "11") (pinfunction "V-_11") (pintype "power_in"))
    )
    (net (code "37") (name "MIDI_OUT") (class "Default")
      (node (ref "R49") (pin "2") (pinfunction "2_2") (pintype "passive"))
      (node (ref "U$17") (pin "1") (pinfunction "1/TX1/T_1") (pintype "bidirectional"))
    )
    (net (code "38") (name "Net-(JP1-LEFT)") (class "Default")
      (node (ref "JP1") (pin "TIP") (pinfunction "LEFT_TIP") (pintype "bidirectional"))
      (node (ref "S1") (pin "P2") (pinfunction "5_P2") (pintype "bidirectional"))
    )
    (net (code "39") (name "Net-(JP1-RIGHT)") (class "Default")
      (node (ref "JP1") (pin "RING") (pinfunction "RIGHT_RING") (pintype "bidirectional"))
      (node (ref "S1") (pin "P1") (pinfunction "2_P1") (pintype "bidirectional"))
    )
    (net (code "40") (name "Net-(S1-1)") (class "Default")
      (node (ref "R52") (pin "1") (pinfunction "1_1") (pintype "passive"))
      (node (ref "S1") (pin "P1-TA") (pinfunction "1_P1-TA") (pintype "bidirectional"))
      (node (ref "S1") (pin "P2-TB") (pinfunction "6_P2-TB") (pintype "bidirectional"))
    )
    (net (code "41") (name "Net-(S1-3)") (class "Default")
      (node (ref "R49") (pin "1") (pinfunction "1_1") (pintype "passive"))
      (node (ref "S1") (pin "P1-TB") (pinfunction "3_P1-TB") (pintype "bidirectional"))
      (node (ref "S1") (pin "P2-TA") (pinfunction "4_P2-TA") (pintype "bidirectional"))
    )
    (net (code "42") (name "Net-(U2A--IN)") (class "Default")
      (node (ref "R1") (pin "1") (pinfunction "1_1") (pintype "passive"))
      (node (ref "U2") (pin "1") (pinfunction "OUT_1") (pintype "output"))
      (node (ref "U2") (pin "2") (pinfunction "-IN_2") (pintype "input"))
    )
    (net (code "43") (name "Net-(U2B-+IN)") (class "Default")
      (node (ref "R35") (pin "2") (pinfunction "2_2") (pintype "passive"))
      (node (ref "R36") (pin "2") (pinfunction "2_2") (pintype "passive"))
      (node (ref "U2") (pin "5") (pinfunction "+IN_5") (pintype "input"))
    )
    (net (code "44") (name "Net-(U2C-+IN)") (class "Default")
      (node (ref "R21") (pin "2") (pinfunction "2_2") (pintype "passive"))
      (node (ref "R22") (pin "2") (pinfunction "2_2") (pintype "passive"))
      (node (ref "U2") (pin "10") (pinfunction "+IN_10") (pintype "input"))
    )
    (net (code "45") (name "Net-(U2D--IN)") (class "Default")
      (node (ref "R2") (pin "1") (pinfunction "1_1") (pintype "passive"))
      (node (ref "U2") (pin "13") (pinfunction "-IN_13") (pintype "input"))
      (node (ref "U2") (pin "14") (pinfunction "OUT_14") (pintype "output"))
    )
    (net (code "46") (name "Net-(U3A--IN)") (class "Default")
      (node (ref "R3") (pin "1") (pinfunction "1_1") (pintype "passive"))
      (node (ref "U3") (pin "1") (pinfunction "OUT_1") (pintype "output"))
      (node (ref "U3") (pin "2") (pinfunction "-IN_2") (pintype "input"))
    )
    (net (code "47") (name "Net-(U3B-+IN)") (class "Default")
      (node (ref "R37") (pin "2") (pinfunction "2_2") (pintype "passive"))
      (node (ref "R38") (pin "2") (pinfunction "2_2") (pintype "passive"))
      (node (ref "U3") (pin "5") (pinfunction "+IN_5") (pintype "input"))
    )
    (net (code "48") (name "Net-(U3C-+IN)") (class "Default")
      (node (ref "R23") (pin "2") (pinfunction "2_2") (pintype "passive"))
      (node (ref "R24") (pin "2") (pinfunction "2_2") (pintype "passive"))
      (node (ref "U3") (pin "10") (pinfunction "+IN_10") (pintype "input"))
    )
    (net (code "49") (name "Net-(U3D--IN)") (class "Default")
      (node (ref "R4") (pin "1") (pinfunction "1_1") (pintype "passive"))
      (node (ref "U3") (pin "13") (pinfunction "-IN_13") (pintype "input"))
      (node (ref "U3") (pin "14") (pinfunction "OUT_14") (pintype "output"))
    )
    (net (code "50") (name "Net-(U4A--IN)") (class "Default")
      (node (ref "R5") (pin "1") (pinfunction "1_1") (pintype "passive"))
      (node (ref "U4") (pin "1") (pinfunction "OUT_1") (pintype "output"))
      (node (ref "U4") (pin "2") (pinfunction "-IN_2") (pintype "input"))
    )
    (net (code "51") (name "Net-(U4B-+IN)") (class "Default")
      (node (ref "R39") (pin "2") (pinfunction "2_2") (pintype "passive"))
      (node (ref "R40") (pin "2") (pinfunction "2_2") (pintype "passive"))
      (node (ref "U4") (pin "5") (pinfunction "+IN_5") (pintype "input"))
    )
    (net (code "52") (name "Net-(U4C-+IN)") (class "Default")
      (node (ref "R25") (pin "2") (pinfunction "2_2") (pintype "passive"))
      (node (ref "R26") (pin "2") (pinfunction "2_2") (pintype "passive"))
      (node (ref "U4") (pin "10") (pinfunction "+IN_10") (pintype "input"))
    )
    (net (code "53") (name "Net-(U4D--IN)") (class "Default")
      (node (ref "R6") (pin "1") (pinfunction "1_1") (pintype "passive"))
      (node (ref "U4") (pin "13") (pinfunction "-IN_13") (pintype "input"))
      (node (ref "U4") (pin "14") (pinfunction "OUT_14") (pintype "output"))
    )
    (net (code "54") (name "Net-(U5A--IN)") (class "Default")
      (node (ref "R7") (pin "1") (pinfunction "1_1") (pintype "passive"))
      (node (ref "U5") (pin "1") (pinfunction "OUT_1") (pintype "output"))
      (node (ref "U5") (pin "2") (pinfunction "-IN_2") (pintype "input"))
    )
    (net (code "55") (name "Net-(U5B-+IN)") (class "Default")
      (node (ref "R41") (pin "2") (pinfunction "2_2") (pintype "passive"))
      (node (ref "R42") (pin "2") (pinfunction "2_2") (pintype "passive"))
      (node (ref "U5") (pin "5") (pinfunction "+IN_5") (pintype "input"))
    )
    (net (code "56") (name "Net-(U5C-+IN)") (class "Default")
      (node (ref "R27") (pin "2") (pinfunction "2_2") (pintype "passive"))
      (node (ref "R28") (pin "2") (pinfunction "2_2") (pintype "passive"))
      (node (ref "U5") (pin "10") (pinfunction "+IN_10") (pintype "input"))
    )
    (net (code "57") (name "Net-(U5D--IN)") (class "Default")
      (node (ref "R8") (pin "1") (pinfunction "1_1") (pintype "passive"))
      (node (ref "U5") (pin "13") (pinfunction "-IN_13") (pintype "input"))
      (node (ref "U5") (pin "14") (pinfunction "OUT_14") (pintype "output"))
    )
    (net (code "58") (name "Net-(U6A--IN)") (class "Default")
      (node (ref "R9") (pin "1") (pinfunction "1_1") (pintype "passive"))
      (node (ref "U6") (pin "1") (pinfunction "OUT_1") (pintype "output"))
      (node (ref "U6") (pin "2") (pinfunction "-IN_2") (pintype "input"))
    )
    (net (code "59") (name "Net-(U6B-+IN)") (class "Default")
      (node (ref "R43") (pin "2") (pinfunction "2_2") (pintype "passive"))
      (node (ref "R44") (pin "2") (pinfunction "2_2") (pintype "passive"))
      (node (ref "U6") (pin "5") (pinfunction "+IN_5") (pintype "input"))
    )
    (net (code "60") (name "Net-(U6C-+IN)") (class "Default")
      (node (ref "R29") (pin "2") (pinfunction "2_2") (pintype "passive"))
      (node (ref "R30") (pin "2") (pinfunction "2_2") (pintype "passive"))
      (node (ref "U6") (pin "10") (pinfunction "+IN_10") (pintype "input"))
    )
    (net (code "61") (name "Net-(U6D--IN)") (class "Default")
      (node (ref "R10") (pin "1") (pinfunction "1_1") (pintype "passive"))
      (node (ref "U6") (pin "13") (pinfunction "-IN_13") (pintype "input"))
      (node (ref "U6") (pin "14") (pinfunction "OUT_14") (pintype "output"))
    )
    (net (code "62") (name "Net-(U7A--IN)") (class "Default")
      (node (ref "R11") (pin "1") (pinfunction "1_1") (pintype "passive"))
      (node (ref "U7") (pin "1") (pinfunction "OUT_1") (pintype "output"))
      (node (ref "U7") (pin "2") (pinfunction "-IN_2") (pintype "input"))
    )
    (net (code "63") (name "Net-(U7B-+IN)") (class "Default")
      (node (ref "R45") (pin "2") (pinfunction "2_2") (pintype "passive"))
      (node (ref "R46") (pin "2") (pinfunction "2_2") (pintype "passive"))
      (node (ref "U7") (pin "5") (pinfunction "+IN_5") (pintype "input"))
    )
    (net (code "64") (name "Net-(U7C-+IN)") (class "Default")
      (node (ref "R31") (pin "2") (pinfunction "2_2") (pintype "passive"))
      (node (ref "R32") (pin "2") (pinfunction "2_2") (pintype "passive"))
      (node (ref "U7") (pin "10") (pinfunction "+IN_10") (pintype "input"))
    )
    (net (code "65") (name "Net-(U7D--IN)") (class "Default")
      (node (ref "R12") (pin "1") (pinfunction "1_1") (pintype "passive"))
      (node (ref "U7") (pin "13") (pinfunction "-IN_13") (pintype "input"))
      (node (ref "U7") (pin "14") (pinfunction "OUT_14") (pintype "output"))
    )
    (net (code "66") (name "Net-(U8A--IN)") (class "Default")
      (node (ref "R13") (pin "1") (pinfunction "1_1") (pintype "passive"))
      (node (ref "U8") (pin "1") (pinfunction "OUT_1") (pintype "output"))
      (node (ref "U8") (pin "2") (pinfunction "-IN_2") (pintype "input"))
    )
    (net (code "67") (name "Net-(U8B-+IN)") (class "Default")
      (node (ref "R47") (pin "2") (pinfunction "2_2") (pintype "passive"))
      (node (ref "R48") (pin "2") (pinfunction "2_2") (pintype "passive"))
      (node (ref "U8") (pin "5") (pinfunction "+IN_5") (pintype "input"))
    )
    (net (code "68") (name "Net-(U8C-+IN)") (class "Default")
      (node (ref "R33") (pin "2") (pinfunction "2_2") (pintype "passive"))
      (node (ref "R34") (pin "2") (pinfunction "2_2") (pintype "passive"))
      (node (ref "U8") (pin "10") (pinfunction "+IN_10") (pintype "input"))
    )
    (net (code "69") (name "Net-(U8D--IN)") (class "Default")
      (node (ref "R14") (pin "1") (pinfunction "1_1") (pintype "passive"))
      (node (ref "U8") (pin "13") (pinfunction "-IN_13") (pintype "input"))
      (node (ref "U8") (pin "14") (pinfunction "OUT_14") (pintype "output"))
    )
    (net (code "70") (name "Net-(U9A--IN)") (class "Default")
      (node (ref "R15") (pin "1") (pinfunction "1_1") (pintype "passive"))
      (node (ref "U9") (pin "1") (pinfunction "OUT_1") (pintype "output"))
      (node (ref "U9") (pin "2") (pinfunction "-IN_2") (pintype "input"))
    )
    (net (code "71") (name "Net-(U9B-+IN)") (class "Default")
      (node (ref "R50") (pin "2") (pinfunction "2_2") (pintype "passive"))
      (node (ref "R51") (pin "2") (pinfunction "2_2") (pintype "passive"))
      (node (ref "U9") (pin "5") (pinfunction "+IN_5") (pintype "input"))
    )
    (net (code "72") (name "Net-(U9C-+IN)") (class "Default")
      (node (ref "R19") (pin "2") (pinfunction "2_2") (pintype "passive"))
      (node (ref "R20") (pin "2") (pinfunction "2_2") (pintype "passive"))
      (node (ref "U9") (pin "10") (pinfunction "+IN_10") (pintype "input"))
    )
    (net (code "73") (name "Net-(U9D--IN)") (class "Default")
      (node (ref "R16") (pin "1") (pinfunction "1_1") (pintype "passive"))
      (node (ref "U9") (pin "13") (pinfunction "-IN_13") (pintype "input"))
      (node (ref "U9") (pin "14") (pinfunction "OUT_14") (pintype "output"))
    )
    (net (code "74") (name "S0") (class "Default")
      (node (ref "U$17") (pin "8") (pinfunction "8/TX3_8") (pintype "bidirectional"))
      (node (ref "U1") (pin "10") (pinfunction "S0_10") (pintype "input"))
    )
    (net (code "75") (name "S1") (class "Default")
      (node (ref "U$17") (pin "7") (pinfunction "7/RX3_7") (pintype "bidirectional"))
      (node (ref "U1") (pin "11") (pinfunction "S1_11") (pintype "input"))
    )
    (net (code "76") (name "S2") (class "Default")
      (node (ref "U$17") (pin "6") (pinfunction "6/PWM_6") (pintype "bidirectional"))
      (node (ref "U1") (pin "14") (pinfunction "S2_14") (pintype "input"))
    )
    (net (code "77") (name "S3") (class "Default")
      (node (ref "U$17") (pin "5") (pinfunction "5/PWM_5") (pintype "bidirectional"))
      (node (ref "U1") (pin "13") (pinfunction "S3_13") (pintype "input"))
    )
    (net (code "78") (name "SCL") (class "Default")
      (node (ref "D1") (pin "A") (pinfunction "A_A") (pintype "passive"))
      (node (ref "D2") (pin "C") (pinfunction "C_C") (pintype "passive"))
      (node (ref "JP2") (pin "RING") (pinfunction "RIGHT_RING") (pintype "bidirectional"))
      (node (ref "R17") (pin "1") (pinfunction "1_1") (pintype "passive"))
      (node (ref "U$17") (pin "19/A5") (pinfunction "19/A5/T/SCL0_19/A5") (pintype "bidirectional"))
    )
    (net (code "79") (name "SDA") (class "Default")
      (node (ref "D3") (pin "C") (pinfunction "C_C") (pintype "passive"))
      (node (ref "D4") (pin "A") (pinfunction "A_A") (pintype "passive"))
      (node (ref "JP2") (pin "TIP") (pinfunction "LEFT_TIP") (pintype "bidirectional"))
      (node (ref "R18") (pin "1") (pinfunction "1_1") (pintype "passive"))
      (node (ref "U$17") (pin "18/A4") (pinfunction "18/A4/T/SDA0_18/A4") (pintype "bidirectional"))
    )
    (net (code "80") (name "W0") (class "Default")
      (node (ref "R35") (pin "1") (pinfunction "1_1") (pintype "passive"))
      (node (ref "U$1") (pin "2") (pinfunction "2_2") (pintype "bidirectional"))
      (node (ref "U2") (pin "3") (pinfunction "+IN_3") (pintype "input"))
    )
    (net (code "81") (name "W1") (class "Default")
      (node (ref "R21") (pin "1") (pinfunction "1_1") (pintype "passive"))
      (node (ref "U$2") (pin "2") (pinfunction "2_2") (pintype "bidirectional"))
      (node (ref "U2") (pin "12") (pinfunction "+IN_12") (pintype "input"))
    )
    (net (code "82") (name "W2") (class "Default")
      (node (ref "R37") (pin "1") (pinfunction "1_1") (pintype "passive"))
      (node (ref "U$3") (pin "2") (pinfunction "2_2") (pintype "bidirectional"))
      (node (ref "U3") (pin "3") (pinfunction "+IN_3") (pintype "input"))
    )
    (net (code "83") (name "W3") (class "Default")
      (node (ref "R23") (pin "1") (pinfunction "1_1") (pintype "passive"))
      (node (ref "U$4") (pin "2") (pinfunction "2_2") (pintype "bidirectional"))
      (node (ref "U3") (pin "12") (pinfunction "+IN_12") (pintype "input"))
    )
    (net (code "84") (name "W4") (class "Default")
      (node (ref "R39") (pin "1") (pinfunction "1_1") (pintype "passive"))
      (node (ref "U$5") (pin "2") (pinfunction "2_2") (pintype "bidirectional"))
      (node (ref "U4") (pin "3") (pinfunction "+IN_3") (pintype "input"))
    )
    (net (code "85") (name "W5") (class "Default")
      (node (ref "R25") (pin "1") (pinfunction "1_1") (pintype "passive"))
      (node (ref "U$6") (pin "2") (pinfunction "2_2") (pintype "bidirectional"))
      (node (ref "U4") (pin "12") (pinfunction "+IN_12") (pintype "input"))
    )
    (net (code "86") (name "W6") (class "Default")
      (node (ref "R41") (pin "1") (pinfunction "1_1") (pintype "passive"))
      (node (ref "U$7") (pin "2") (pinfunction "2_2") (pintype "bidirectional"))
      (node (ref "U5") (pin "3") (pinfunction "+IN_3") (pintype "input"))
    )
    (net (code "87") (name "W7") (class "Default")
      (node (ref "R27") (pin "1") (pinfunction "1_1") (pintype "passive"))
      (node (ref "U$8") (pin "2") (pinfunction "2_2") (pintype "bidirectional"))
      (node (ref "U5") (pin "12") (pinfunction "+IN_12") (pintype "input"))
    )
    (net (code "88") (name "W8") (class "Default")
      (node (ref "R43") (pin "1") (pinfunction "1_1") (pintype "passive"))
      (node (ref "U$9") (pin "2") (pinfunction "2_2") (pintype "bidirectional"))
      (node (ref "U6") (pin "3") (pinfunction "+IN_3") (pintype "input"))
    )
    (net (code "89") (name "W9") (class "Default")
      (node (ref "R29") (pin "1") (pinfunction "1_1") (pintype "passive"))
      (node (ref "U$10") (pin "2") (pinfunction "2_2") (pintype "bidirectional"))
      (node (ref "U6") (pin "12") (pinfunction "+IN_12") (pintype "input"))
    )
    (net (code "90") (name "W10") (class "Default")
      (node (ref "R45") (pin "1") (pinfunction "1_1") (pintype "passive"))
      (node (ref "U$11") (pin "2") (pinfunction "2_2") (pintype "bidirectional"))
      (node (ref "U7") (pin "3") (pinfunction "+IN_3") (pintype "input"))
    )
    (net (code "91") (name "W11") (class "Default")
      (node (ref "R31") (pin "1") (pinfunction "1_1") (pintype "passive"))
      (node (ref "U$12") (pin "2") (pinfunction "2_2") (pintype "bidirectional"))
      (node (ref "U7") (pin "12") (pinfunction "+IN_12") (pintype "input"))
    )
    (net (code "92") (name "W12") (class "Default")
      (node (ref "R47") (pin "1") (pinfunction "1_1") (pintype "passive"))
      (node (ref "U$13") (pin "2") (pinfunction "2_2") (pintype "bidirectional"))
      (node (ref "U8") (pin "3") (pinfunction "+IN_3") (pintype "input"))
    )
    (net (code "93") (name "W13") (class "Default")
      (node (ref "R33") (pin "1") (pinfunction "1_1") (pintype "passive"))
      (node (ref "U$14") (pin "2") (pinfunction "2_2") (pintype "bidirectional"))
      (node (ref "U8") (pin "12") (pinfunction "+IN_12") (pintype "input"))
    )
    (net (code "94") (name "W14") (class "Default")
      (node (ref "R50") (pin "1") (pinfunction "1_1") (pintype "passive"))
      (node (ref "U$15") (pin "2") (pinfunction "2_2") (pintype "bidirectional"))
      (node (ref "U9") (pin "3") (pinfunction "+IN_3") (pintype "input"))
    )
    (net (code "95") (name "W15") (class "Default")
      (node (ref "R19") (pin "1") (pinfunction "1_1") (pintype "passive"))
      (node (ref "U$16") (pin "2") (pinfunction "2_2") (pintype "bidirectional"))
      (node (ref "U9") (pin "12") (pinfunction "+IN_12") (pintype "input"))
    )
    (net (code "96") (name "unconnected-(J1-SWITCH-PadSW)") (class "Default")
      (node (ref "J1") (pin "SW") (pinfunction "SWITCH_SW") (pintype "passive"))
    )
    (net (code "97") (name "unconnected-(J2-SWITCH-PadSW)") (class "Default")
      (node (ref "J2") (pin "SW") (pinfunction "SWITCH_SW") (pintype "passive"))
    )
    (net (code "98") (name "unconnected-(J3-SWITCH-PadSW)") (class "Default")
      (node (ref "J3") (pin "SW") (pinfunction "SWITCH_SW") (pintype "passive"))
    )
    (net (code "99") (name "unconnected-(J4-SWITCH-PadSW)") (class "Default")
      (node (ref "J4") (pin "SW") (pinfunction "SWITCH_SW") (pintype "passive"))
    )
    (net (code "100") (name "unconnected-(J5-SWITCH-PadSW)") (class "Default")
      (node (ref "J5") (pin "SW") (pinfunction "SWITCH_SW") (pintype "passive"))
    )
    (net (code "101") (name "unconnected-(J6-SWITCH-PadSW)") (class "Default")
      (node (ref "J6") (pin "SW") (pinfunction "SWITCH_SW") (pintype "passive"))
    )
    (net (code "102") (name "unconnected-(J7-SWITCH-PadSW)") (class "Default")
      (node (ref "J7") (pin "SW") (pinfunction "SWITCH_SW") (pintype "passive"))
    )
    (net (code "103") (name "unconnected-(J8-SWITCH-PadSW)") (class "Default")
      (node (ref "J8") (pin "SW") (pinfunction "SWITCH_SW") (pintype "passive"))
    )
    (net (code "104") (name "unconnected-(J9-SWITCH-PadSW)") (class "Default")
      (node (ref "J9") (pin "SW") (pinfunction "SWITCH_SW") (pintype "passive"))
    )
    (net (code "105") (name "unconnected-(J10-SWITCH-PadSW)") (class "Default")
      (node (ref "J10") (pin "SW") (pinfunction "SWITCH_SW") (pintype "passive"))
    )
    (net (code "106") (name "unconnected-(J11-SWITCH-PadSW)") (class "Default")
      (node (ref "J11") (pin "SW") (pinfunction "SWITCH_SW") (pintype "passive"))
    )
    (net (code "107") (name "unconnected-(J12-SWITCH-PadSW)") (class "Default")
      (node (ref "J12") (pin "SW") (pinfunction "SWITCH_SW") (pintype "passive"))
    )
    (net (code "108") (name "unconnected-(J13-SWITCH-PadSW)") (class "Default")
      (node (ref "J13") (pin "SW") (pinfunction "SWITCH_SW") (pintype "passive"))
    )
    (net (code "109") (name "unconnected-(J14-SWITCH-PadSW)") (class "Default")
      (node (ref "J14") (pin "SW") (pinfunction "SWITCH_SW") (pintype "passive"))
    )
    (net (code "110") (name "unconnected-(J15-SWITCH-PadSW)") (class "Default")
      (node (ref "J15") (pin "SW") (pinfunction "SWITCH_SW") (pintype "passive"))
    )
    (net (code "111") (name "unconnected-(J16-SWITCH-PadSW)") (class "Default")
      (node (ref "J16") (pin "SW") (pinfunction "SWITCH_SW") (pintype "passive"))
    )
    (net (code "112") (name "unconnected-(U$17-0{slash}RX1{slash}T-Pad0)") (class "Default")
      (node (ref "U$17") (pin "0") (pinfunction "0/RX1/T_0") (pintype "bidirectional"))
    )
    (net (code "113") (name "unconnected-(U$17-3{slash}CAN-TX{slash}PWM-Pad3)") (class "Default")
      (node (ref "U$17") (pin "3") (pinfunction "3/CAN-TX/PWM_3") (pintype "bidirectional"))
    )
    (net (code "114") (name "unconnected-(U$17-4{slash}CAN-RX{slash}PWM-Pad4)") (class "Default")
      (node (ref "U$17") (pin "4") (pinfunction "4/CAN-RX/PWM_4") (pintype "bidirectional"))
    )
    (net (code "115") (name "unconnected-(U$17-9{slash}RX2{slash}PWM-Pad9)") (class "Default")
      (node (ref "U$17") (pin "9") (pinfunction "9/RX2/PWM_9") (pintype "bidirectional"))
    )
    (net (code "116") (name "unconnected-(U$17-10{slash}TX2{slash}PWM-Pad10)") (class "Default")
      (node (ref "U$17") (pin "10") (pinfunction "10/TX2/PWM_10") (pintype "bidirectional"))
    )
    (net (code "117") (name "unconnected-(U$17-11{slash}MOSI-Pad11)") (class "Default")
      (node (ref "U$17") (pin "11") (pinfunction "11/MOSI_11") (pintype "bidirectional"))
    )
    (net (code "118") (name "unconnected-(U$17-12{slash}MISO-Pad12)") (class "Default")
      (node (ref "U$17") (pin "12") (pinfunction "12/MISO_12") (pintype "bidirectional"))
    )
    (net (code "119") (name "unconnected-(U$17-13{slash}SCK{slash}LED-Pad13)") (class "Default")
      (node (ref "U$17") (pin "13") (pinfunction "13/SCK/LED_13") (pintype "bidirectional"))
    )
    (net (code "120") (name "unconnected-(U$17-15{slash}A1{slash}T-Pad15{slash}A1)") (class "Default")
      (node (ref "U$17") (pin "15/A1") (pinfunction "15/A1/T_15/A1") (pintype "bidirectional"))
    )
    (net (code "121") (name "unconnected-(U$17-16{slash}A2{slash}T-Pad16{slash}A2)") (class "Default")
      (node (ref "U$17") (pin "16/A2") (pinfunction "16/A2/T_16/A2") (pintype "bidirectional"))
    )
    (net (code "122") (name "unconnected-(U$17-17{slash}A3{slash}T-Pad17{slash}A3)") (class "Default")
      (node (ref "U$17") (pin "17/A3") (pinfunction "17/A3/T_17/A3") (pintype "bidirectional"))
    )
    (net (code "123") (name "unconnected-(U$17-20{slash}A6{slash}PWM-Pad20{slash}A6)") (class "Default")
      (node (ref "U$17") (pin "20/A6") (pinfunction "20/A6/PWM_20/A6") (pintype "bidirectional"))
    )
    (net (code "124") (name "unconnected-(U$17-21{slash}A7{slash}PWM-Pad21{slash}A7)") (class "Default")
      (node (ref "U$17") (pin "21/A7") (pinfunction "21/A7/PWM_21/A7") (pintype "bidirectional"))
    )
    (net (code "125") (name "unconnected-(U$17-22{slash}A8{slash}T{slash}PWM-Pad22{slash}A8)") (class "Default")
      (node (ref "U$17") (pin "22/A8") (pinfunction "22/A8/T/PWM_22/A8") (pintype "bidirectional"))
    )
    (net (code "126") (name "unconnected-(U$17-23{slash}A9{slash}T{slash}PWM-Pad23{slash}A9)") (class "Default")
      (node (ref "U$17") (pin "23/A9") (pinfunction "23/A9/T/PWM_23/A9") (pintype "bidirectional"))
    )
    (net (code "127") (name "unconnected-(U$17-Pad2)") (class "Default")
      (node (ref "U$17") (pin "2") (pinfunction "2_2") (pintype "bidirectional"))
    )
  )
)
